# serpentine2.net
KiCad netlist of a schematic drawn in Altium Designer
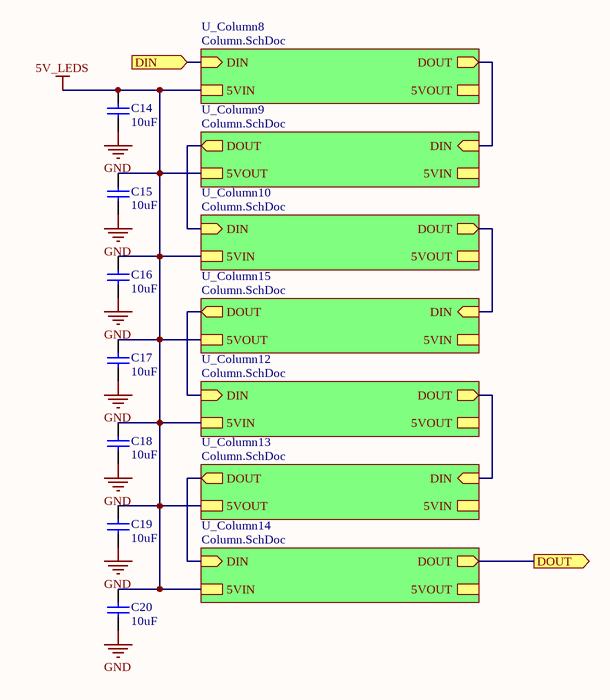
[diagram p0: serpentine2.SchDoc]

(export (version "E")
  (design (tool "Eeschema 10.0.6"))
  (components
    (comp (ref "C14")
      (value "10uF")
      (footprint "CAP0603")
      (description "C342827")
      (fields (field (name "TOLERANCE") "10%"))
      (libsource (lib "blandat") (part "CAP"))
    )
    (comp (ref "C15")
      (value "10uF")
      (footprint "CAP1206")
      (description "C342827")
      (fields (field (name "TOLERANCE") "10%"))
      (libsource (lib "blandat") (part "CAP"))
    )
    (comp (ref "C16")
      (value "10uF")
      (footprint "CAP1206")
      (description "C342827")
      (fields (field (name "TOLERANCE") "10%"))
      (libsource (lib "blandat") (part "CAP"))
    )
    (comp (ref "C17")
      (value "10uF")
      (footprint "CAP1206")
      (description "C342827")
      (fields (field (name "TOLERANCE") "10%"))
      (libsource (lib "blandat") (part "CAP"))
    )
    (comp (ref "C18")
      (value "10uF")
      (footprint "CAP1206")
      (description "C342827")
      (fields (field (name "TOLERANCE") "10%"))
      (libsource (lib "blandat") (part "CAP"))
    )
    (comp (ref "C19")
      (value "10uF")
      (footprint "CAP1206")
      (description "C342827")
      (fields (field (name "TOLERANCE") "10%"))
      (libsource (lib "blandat") (part "CAP"))
    )
    (comp (ref "C20")
      (value "10uF")
      (footprint "CAP1206")
      (description "C342827")
      (fields (field (name "TOLERANCE") "10%"))
      (libsource (lib "blandat") (part "CAP"))
    )
  )
  (nets
    (net (code "16") (name "5V_LEDS") (class "Default")
      (node (ref "C14") (pin "2") (pinfunction "2_2") (pintype "passive"))
      (node (ref "C15") (pin "2") (pinfunction "2_2") (pintype "passive"))
      (node (ref "C16") (pin "2") (pinfunction "2_2") (pintype "passive"))
      (node (ref "C17") (pin "2") (pinfunction "2_2") (pintype "passive"))
      (node (ref "C18") (pin "2") (pinfunction "2_2") (pintype "passive"))
      (node (ref "C19") (pin "2") (pinfunction "2_2") (pintype "passive"))
      (node (ref "C20") (pin "2") (pinfunction "2_2") (pintype "passive"))
    )
    (net (code "17") (name "GND") (class "Default")
      (node (ref "C14") (pin "1") (pinfunction "1_1") (pintype "passive"))
      (node (ref "C15") (pin "1") (pinfunction "1_1") (pintype "passive"))
      (node (ref "C16") (pin "1") (pinfunction "1_1") (pintype "passive"))
      (node (ref "C17") (pin "1") (pinfunction "1_1") (pintype "passive"))
      (node (ref "C18") (pin "1") (pinfunction "1_1") (pintype "passive"))
      (node (ref "C19") (pin "1") (pinfunction "1_1") (pintype "passive"))
      (node (ref "C20") (pin "1") (pinfunction "1_1") (pintype "passive"))
    )
  )
)
